# Venti_rev1.net
KiCad netlist of a schematic drawn in EAGLE
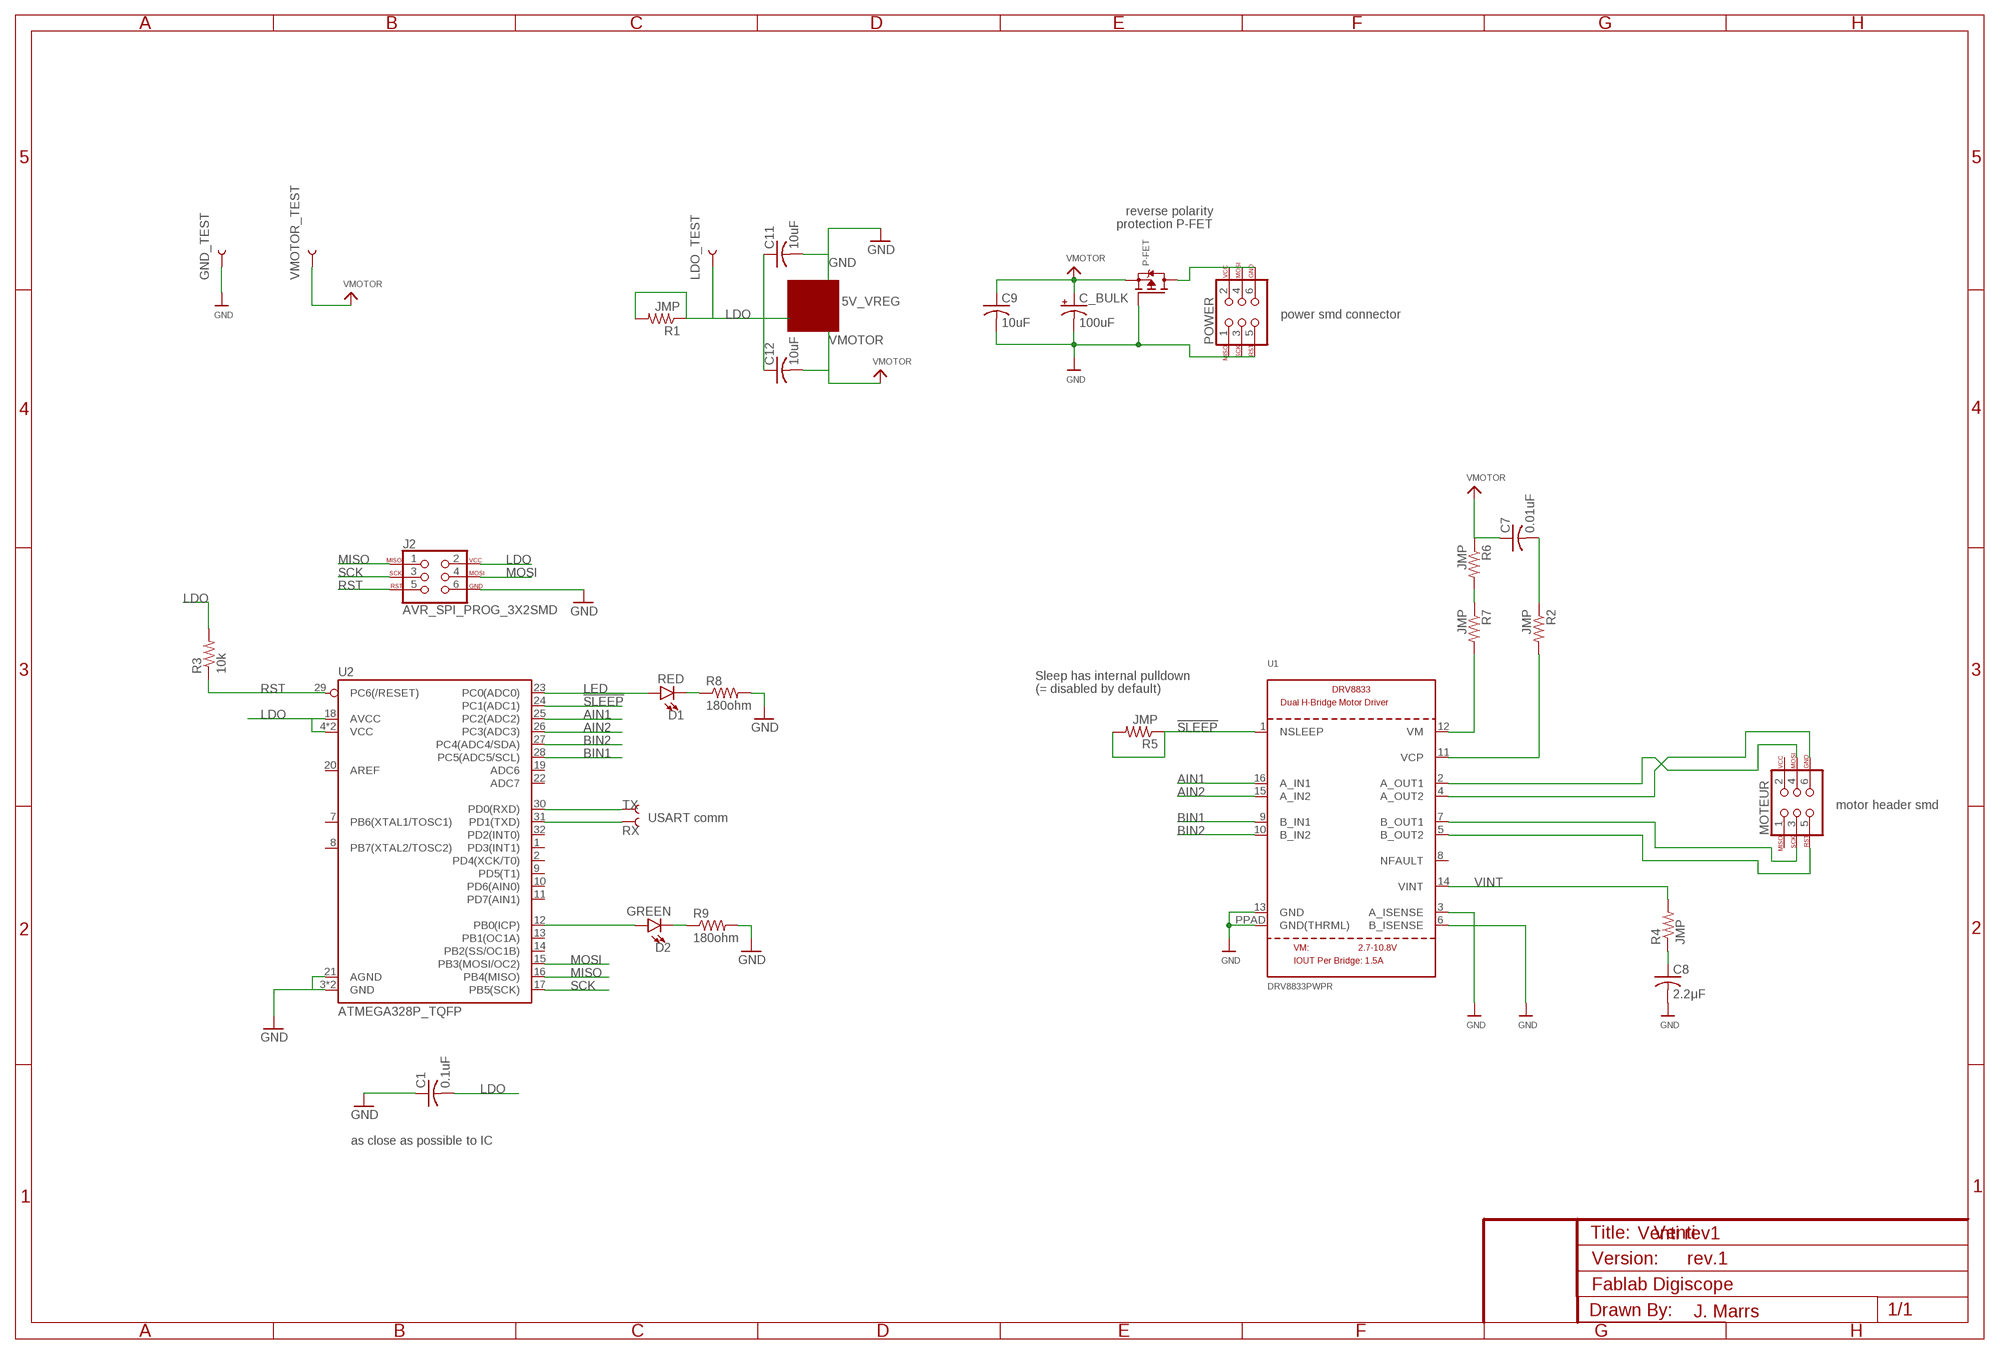
[diagram p0: schematic, sheet 1]

(export (version "E")
  (design (tool "Eeschema 10.0.6"))
  (components
    (comp (ref "5V_VREG")
      (value "MOSFET_PCH-DMG2305UX-7")
      (footprint "eagle-import:SOT23-3")
      (libsource (lib "eagle-import") (part "MOSFET_PCH-DMG2305UX-7"))
    )
    (comp (ref "C1")
      (value "0.1uF")
      (footprint "eagle-import:C1206")
      (libsource (lib "eagle-import") (part "C-USC1206"))
    )
    (comp (ref "C7")
      (value "0.01uF")
      (footprint "eagle-import:C1206")
      (libsource (lib "eagle-import") (part "C-USC1206"))
    )
    (comp (ref "C8")
      (value "2.2μF")
      (footprint "eagle-import:C1206")
      (libsource (lib "eagle-import") (part "C-USC1206"))
    )
    (comp (ref "C9")
      (value "10uF")
      (footprint "eagle-import:C1206")
      (libsource (lib "eagle-import") (part "C-USC1206"))
    )
    (comp (ref "C11")
      (value "10uF")
      (footprint "eagle-import:C1206")
      (libsource (lib "eagle-import") (part "C-USC1206"))
    )
    (comp (ref "C12")
      (value "10uF")
      (footprint "eagle-import:C1206")
      (libsource (lib "eagle-import") (part "C-USC1206"))
    )
    (comp (ref "C_BULK")
      (value "100uF")
      (footprint "eagle-import:CPOL-RADIAL-2.5MM-6.5MM")
      (libsource (lib "eagle-import") (part "100UF-POLAR-RADIAL-2.5MM-25V-20%"))
    )
    (comp (ref "D1")
      (value "RED")
      (footprint "eagle-import:LED-1206")
      (libsource (lib "eagle-import") (part "LED-RED1206"))
    )
    (comp (ref "D2")
      (value "GREEN")
      (footprint "eagle-import:LED-1206")
      (libsource (lib "eagle-import") (part "LED-RED1206"))
    )
    (comp (ref "GND_TEST")
      (value "TEST-POINT3")
      (footprint "eagle-import:PAD.03X.03")
      (libsource (lib "eagle-import") (part "TEST-POINT3"))
    )
    (comp (ref "J2")
      (value "AVR_SPI_PROG_3X2SMD")
      (footprint "eagle-import:2X3_SMT_POSTS")
      (libsource (lib "eagle-import") (part "AVR_SPI_PROG_3X2SMD"))
    )
    (comp (ref "LDO_TEST")
      (value "TEST-POINT3")
      (footprint "eagle-import:PAD.03X.03")
      (libsource (lib "eagle-import") (part "TEST-POINT3"))
    )
    (comp (ref "MOTEUR")
      (value "AVR_SPI_PROG_3X2SMD")
      (footprint "eagle-import:2X3_SMT_POSTS")
      (libsource (lib "eagle-import") (part "AVR_SPI_PROG_3X2SMD"))
    )
    (comp (ref "P-FET")
      (value "MOSFET-PWIDE")
      (footprint "eagle-import:SOT23-WIDE")
      (libsource (lib "eagle-import") (part "MOSFET-PWIDE"))
    )
    (comp (ref "POWER")
      (value "AVR_SPI_PROG_3X2SMD")
      (footprint "eagle-import:2X3_SMT_POSTS")
      (libsource (lib "eagle-import") (part "AVR_SPI_PROG_3X2SMD"))
    )
    (comp (ref "R1")
      (value "JMP")
      (footprint "eagle-import:R1206")
      (libsource (lib "eagle-import") (part "R-US_R1206"))
    )
    (comp (ref "R2")
      (value "JMP")
      (footprint "eagle-import:R1206")
      (libsource (lib "eagle-import") (part "R-US_R1206"))
    )
    (comp (ref "R3")
      (value "10k")
      (footprint "eagle-import:R1206")
      (libsource (lib "eagle-import") (part "R-US_R1206"))
    )
    (comp (ref "R4")
      (value "JMP")
      (footprint "eagle-import:R1206")
      (libsource (lib "eagle-import") (part "R-US_R1206"))
    )
    (comp (ref "R5")
      (value "JMP")
      (footprint "eagle-import:R1206")
      (libsource (lib "eagle-import") (part "R-US_R1206"))
    )
    (comp (ref "R6")
      (value "JMP")
      (footprint "eagle-import:R1206")
      (libsource (lib "eagle-import") (part "R-US_R1206"))
    )
    (comp (ref "R7")
      (value "JMP")
      (footprint "eagle-import:R1206")
      (libsource (lib "eagle-import") (part "R-US_R1206"))
    )
    (comp (ref "R8")
      (value "180ohm")
      (footprint "eagle-import:R1206")
      (libsource (lib "eagle-import") (part "R-US_R1206"))
    )
    (comp (ref "R9")
      (value "180ohm")
      (footprint "eagle-import:R1206")
      (libsource (lib "eagle-import") (part "R-US_R1206"))
    )
    (comp (ref "RX")
      (value "TEST-POINT3")
      (footprint "eagle-import:PAD.03X.03")
      (libsource (lib "eagle-import") (part "TEST-POINT3"))
    )
    (comp (ref "TX")
      (value "TEST-POINT3")
      (footprint "eagle-import:PAD.03X.03")
      (libsource (lib "eagle-import") (part "TEST-POINT3"))
    )
    (comp (ref "U1")
      (value "DRV8833PWPR")
      (footprint "eagle-import:HTSSOP16")
      (libsource (lib "eagle-import") (part "DRV8833"))
    )
    (comp (ref "U2")
      (value "ATMEGA328P_TQFP")
      (footprint "eagle-import:TQFP32-08")
      (libsource (lib "eagle-import") (part "ATMEGA328P_TQFP"))
    )
    (comp (ref "VMOTOR_TEST")
      (value "TEST-POINT3")
      (footprint "eagle-import:PAD.03X.03")
      (libsource (lib "eagle-import") (part "TEST-POINT3"))
    )
  )
  (nets
    (net (code "1") (name "/AIN1") (class "Default")
      (node (ref "U1") (pin "16") (pinfunction "A_IN1_16") (pintype "input"))
      (node (ref "U2") (pin "25") (pinfunction "PC2(ADC2)_25") (pintype "bidirectional"))
    )
    (net (code "2") (name "/AIN2") (class "Default")
      (node (ref "U1") (pin "15") (pinfunction "A_IN2_15") (pintype "input"))
      (node (ref "U2") (pin "26") (pinfunction "PC3(ADC3)_26") (pintype "bidirectional"))
    )
    (net (code "3") (name "/BIN1") (class "Default")
      (node (ref "U1") (pin "9") (pinfunction "B_IN1_9") (pintype "input"))
      (node (ref "U2") (pin "28") (pinfunction "PC5(ADC5/SCL)_28") (pintype "bidirectional"))
    )
    (net (code "4") (name "/BIN2") (class "Default")
      (node (ref "U1") (pin "10") (pinfunction "B_IN2_10") (pintype "input"))
      (node (ref "U2") (pin "27") (pinfunction "PC4(ADC4/SDA)_27") (pintype "bidirectional"))
    )
    (net (code "5") (name "/LDO") (class "Default")
      (node (ref "5V_VREG") (pin "1") (pinfunction "G_1") (pintype "bidirectional"))
      (node (ref "C1") (pin "2") (pinfunction "2_2") (pintype "passive"))
      (node (ref "C11") (pin "1") (pinfunction "1_1") (pintype "passive"))
      (node (ref "C12") (pin "1") (pinfunction "1_1") (pintype "passive"))
      (node (ref "J2") (pin "2") (pinfunction "2_2") (pintype "passive"))
      (node (ref "LDO_TEST") (pin "P$1") (pinfunction "1_P$1") (pintype "bidirectional"))
      (node (ref "R1") (pin "1") (pinfunction "1_1") (pintype "passive"))
      (node (ref "R1") (pin "2") (pinfunction "2_2") (pintype "passive"))
      (node (ref "R3") (pin "2") (pinfunction "2_2") (pintype "passive"))
      (node (ref "U2") (pin "18") (pinfunction "AVCC_18") (pintype "bidirectional"))
      (node (ref "U2") (pin "4") (pinfunction "VCC_4") (pintype "bidirectional"))
      (node (ref "U2") (pin "6") (pinfunction "VCC_6") (pintype "bidirectional"))
    )
    (net (code "6") (name "/LED") (class "Default")
      (node (ref "D1") (pin "A") (pinfunction "A_A") (pintype "passive"))
      (node (ref "U2") (pin "23") (pinfunction "PC0(ADC0)_23") (pintype "bidirectional"))
    )
    (net (code "7") (name "/MISO") (class "Default")
      (node (ref "J2") (pin "1") (pinfunction "1_1") (pintype "passive"))
      (node (ref "U2") (pin "16") (pinfunction "PB4(MISO)_16") (pintype "bidirectional"))
    )
    (net (code "8") (name "/MOSI") (class "Default")
      (node (ref "J2") (pin "4") (pinfunction "4_4") (pintype "passive"))
      (node (ref "U2") (pin "15") (pinfunction "PB3(MOSI/OC2)_15") (pintype "bidirectional"))
    )
    (net (code "9") (name "/RST") (class "Default")
      (node (ref "J2") (pin "5") (pinfunction "5_5") (pintype "passive"))
      (node (ref "R3") (pin "1") (pinfunction "1_1") (pintype "passive"))
      (node (ref "U2") (pin "29") (pinfunction "PC6(/RESET)_29") (pintype "bidirectional"))
    )
    (net (code "10") (name "/SCK") (class "Default")
      (node (ref "J2") (pin "3") (pinfunction "3_3") (pintype "passive"))
      (node (ref "U2") (pin "17") (pinfunction "PB5(SCK)_17") (pintype "bidirectional"))
    )
    (net (code "11") (name "/VINT") (class "Default")
      (node (ref "R4") (pin "2") (pinfunction "2_2") (pintype "passive"))
      (node (ref "U1") (pin "14") (pinfunction "VINT_14") (pintype "power_in"))
    )
    (net (code "12") (name "/~{SLEEP}") (class "Default")
      (node (ref "R5") (pin "1") (pinfunction "1_1") (pintype "passive"))
      (node (ref "R5") (pin "2") (pinfunction "2_2") (pintype "passive"))
      (node (ref "U1") (pin "1") (pinfunction "NSLEEP_1") (pintype "input"))
      (node (ref "U2") (pin "24") (pinfunction "PC1(ADC1)_24") (pintype "bidirectional"))
    )
    (net (code "13") (name "GND") (class "Default")
      (node (ref "5V_VREG") (pin "3") (pinfunction "D_3") (pintype "bidirectional"))
      (node (ref "C1") (pin "1") (pinfunction "1_1") (pintype "passive"))
      (node (ref "C11") (pin "2") (pinfunction "2_2") (pintype "passive"))
      (node (ref "C8") (pin "2") (pinfunction "2_2") (pintype "passive"))
      (node (ref "C9") (pin "2") (pinfunction "2_2") (pintype "passive"))
      (node (ref "C_BULK") (pin "2") (pinfunction "-_2") (pintype "passive"))
      (node (ref "GND_TEST") (pin "P$1") (pinfunction "1_P$1") (pintype "bidirectional"))
      (node (ref "J2") (pin "6") (pinfunction "6_6") (pintype "passive"))
      (node (ref "P-FET") (pin "1") (pinfunction "G_1") (pintype "passive"))
      (node (ref "POWER") (pin "1") (pinfunction "1_1") (pintype "passive"))
      (node (ref "POWER") (pin "3") (pinfunction "3_3") (pintype "passive"))
      (node (ref "POWER") (pin "5") (pinfunction "5_5") (pintype "passive"))
      (node (ref "R8") (pin "2") (pinfunction "2_2") (pintype "passive"))
      (node (ref "R9") (pin "2") (pinfunction "2_2") (pintype "passive"))
      (node (ref "U1") (pin "13") (pinfunction "GND_13") (pintype "power_in"))
      (node (ref "U1") (pin "3") (pinfunction "A_ISENSE_3") (pintype "bidirectional"))
      (node (ref "U1") (pin "6") (pinfunction "B_ISENSE_6") (pintype "bidirectional"))
      (node (ref "U1") (pin "PPAD") (pinfunction "GND(THRML)_PPAD") (pintype "power_in"))
      (node (ref "U2") (pin "21") (pinfunction "AGND_21") (pintype "bidirectional"))
      (node (ref "U2") (pin "3") (pinfunction "GND_3") (pintype "bidirectional"))
      (node (ref "U2") (pin "5") (pinfunction "GND_5") (pintype "bidirectional"))
    )
    (net (code "14") (name "Net-(C7-Pad2)") (class "Default")
      (node (ref "C7") (pin "2") (pinfunction "2_2") (pintype "passive"))
      (node (ref "R2") (pin "1") (pinfunction "1_1") (pintype "passive"))
    )
    (net (code "15") (name "Net-(C8-Pad1)") (class "Default")
      (node (ref "C8") (pin "1") (pinfunction "1_1") (pintype "passive"))
      (node (ref "R4") (pin "1") (pinfunction "1_1") (pintype "passive"))
    )
    (net (code "16") (name "Net-(D1-PadC)") (class "Default")
      (node (ref "D1") (pin "C") (pinfunction "C_C") (pintype "passive"))
      (node (ref "R8") (pin "1") (pinfunction "1_1") (pintype "passive"))
    )
    (net (code "17") (name "Net-(D2-PadC)") (class "Default")
      (node (ref "D2") (pin "C") (pinfunction "C_C") (pintype "passive"))
      (node (ref "R9") (pin "1") (pinfunction "1_1") (pintype "passive"))
    )
    (net (code "18") (name "Net-(P-FET-D)") (class "Default")
      (node (ref "P-FET") (pin "3") (pinfunction "D_3") (pintype "passive"))
      (node (ref "POWER") (pin "2") (pinfunction "2_2") (pintype "passive"))
      (node (ref "POWER") (pin "4") (pinfunction "4_4") (pintype "passive"))
      (node (ref "POWER") (pin "6") (pinfunction "6_6") (pintype "passive"))
    )
    (net (code "19") (name "Net-(R6-Pad2)") (class "Default")
      (node (ref "R6") (pin "2") (pinfunction "2_2") (pintype "passive"))
      (node (ref "R7") (pin "1") (pinfunction "1_1") (pintype "passive"))
    )
    (net (code "20") (name "Net-(RX-1)") (class "Default")
      (node (ref "RX") (pin "P$1") (pinfunction "1_P$1") (pintype "bidirectional"))
      (node (ref "U2") (pin "31") (pinfunction "PD1(TXD)_31") (pintype "bidirectional"))
    )
    (net (code "21") (name "Net-(TX-1)") (class "Default")
      (node (ref "TX") (pin "P$1") (pinfunction "1_P$1") (pintype "bidirectional"))
      (node (ref "U2") (pin "30") (pinfunction "PD0(RXD)_30") (pintype "bidirectional"))
    )
    (net (code "22") (name "Net-(U1-A_OUT1)") (class "Default")
      (node (ref "MOTEUR") (pin "4") (pinfunction "4_4") (pintype "passive"))
      (node (ref "U1") (pin "2") (pinfunction "A_OUT1_2") (pintype "output"))
    )
    (net (code "23") (name "Net-(U1-A_OUT2)") (class "Default")
      (node (ref "MOTEUR") (pin "6") (pinfunction "6_6") (pintype "passive"))
      (node (ref "U1") (pin "4") (pinfunction "A_OUT2_4") (pintype "output"))
    )
    (net (code "24") (name "Net-(U1-B_OUT1)") (class "Default")
      (node (ref "MOTEUR") (pin "3") (pinfunction "3_3") (pintype "passive"))
      (node (ref "U1") (pin "7") (pinfunction "B_OUT1_7") (pintype "output"))
    )
    (net (code "25") (name "Net-(U1-B_OUT2)") (class "Default")
      (node (ref "MOTEUR") (pin "5") (pinfunction "5_5") (pintype "passive"))
      (node (ref "U1") (pin "5") (pinfunction "B_OUT2_5") (pintype "output"))
    )
    (net (code "26") (name "Net-(U1-VCP)") (class "Default")
      (node (ref "R2") (pin "2") (pinfunction "2_2") (pintype "passive"))
      (node (ref "U1") (pin "11") (pinfunction "VCP_11") (pintype "bidirectional"))
    )
    (net (code "27") (name "Net-(U1-VM)") (class "Default")
      (node (ref "R7") (pin "2") (pinfunction "2_2") (pintype "passive"))
      (node (ref "U1") (pin "12") (pinfunction "VM_12") (pintype "power_in"))
    )
    (net (code "28") (name "Net-(U2-PB0(ICP))") (class "Default")
      (node (ref "D2") (pin "A") (pinfunction "A_A") (pintype "passive"))
      (node (ref "U2") (pin "12") (pinfunction "PB0(ICP)_12") (pintype "bidirectional"))
    )
    (net (code "29") (name "VMOTOR") (class "Default")
      (node (ref "5V_VREG") (pin "2") (pinfunction "S_2") (pintype "bidirectional"))
      (node (ref "C12") (pin "2") (pinfunction "2_2") (pintype "passive"))
      (node (ref "C7") (pin "1") (pinfunction "1_1") (pintype "passive"))
      (node (ref "C9") (pin "1") (pinfunction "1_1") (pintype "passive"))
      (node (ref "C_BULK") (pin "1") (pinfunction "+_1") (pintype "passive"))
      (node (ref "P-FET") (pin "2") (pinfunction "S_2") (pintype "passive"))
      (node (ref "R6") (pin "1") (pinfunction "1_1") (pintype "passive"))
      (node (ref "VMOTOR_TEST") (pin "P$1") (pinfunction "1_P$1") (pintype "bidirectional"))
    )
    (net (code "30") (name "unconnected-(MOTEUR-Pad1)") (class "Default")
      (node (ref "MOTEUR") (pin "1") (pinfunction "1_1") (pintype "passive"))
    )
    (net (code "31") (name "unconnected-(MOTEUR-Pad2)") (class "Default")
      (node (ref "MOTEUR") (pin "2") (pinfunction "2_2") (pintype "passive"))
    )
    (net (code "32") (name "unconnected-(U1-NFAULT-Pad8)") (class "Default")
      (node (ref "U1") (pin "8") (pinfunction "NFAULT_8") (pintype "bidirectional"))
    )
    (net (code "33") (name "unconnected-(U2-ADC6-Pad19)") (class "Default")
      (node (ref "U2") (pin "19") (pinfunction "ADC6_19") (pintype "bidirectional"))
    )
    (net (code "34") (name "unconnected-(U2-ADC7-Pad22)") (class "Default")
      (node (ref "U2") (pin "22") (pinfunction "ADC7_22") (pintype "bidirectional"))
    )
    (net (code "35") (name "unconnected-(U2-AREF-Pad20)") (class "Default")
      (node (ref "U2") (pin "20") (pinfunction "AREF_20") (pintype "bidirectional"))
    )
    (net (code "36") (name "unconnected-(U2-PB1(OC1A)-Pad13)") (class "Default")
      (node (ref "U2") (pin "13") (pinfunction "PB1(OC1A)_13") (pintype "bidirectional"))
    )
    (net (code "37") (name "unconnected-(U2-PB2(SS{slash}OC1B)-Pad14)") (class "Default")
      (node (ref "U2") (pin "14") (pinfunction "PB2(SS/OC1B)_14") (pintype "bidirectional"))
    )
    (net (code "38") (name "unconnected-(U2-PB6(XTAL1{slash}TOSC1)-Pad7)") (class "Default")
      (node (ref "U2") (pin "7") (pinfunction "PB6(XTAL1/TOSC1)_7") (pintype "bidirectional"))
    )
    (net (code "39") (name "unconnected-(U2-PB7(XTAL2{slash}TOSC2)-Pad8)") (class "Default")
      (node (ref "U2") (pin "8") (pinfunction "PB7(XTAL2/TOSC2)_8") (pintype "bidirectional"))
    )
    (net (code "40") (name "unconnected-(U2-PD2(INT0)-Pad32)") (class "Default")
      (node (ref "U2") (pin "32") (pinfunction "PD2(INT0)_32") (pintype "bidirectional"))
    )
    (net (code "41") (name "unconnected-(U2-PD3(INT1)-Pad1)") (class "Default")
      (node (ref "U2") (pin "1") (pinfunction "PD3(INT1)_1") (pintype "bidirectional"))
    )
    (net (code "42") (name "unconnected-(U2-PD4(XCK{slash}T0)-Pad2)") (class "Default")
      (node (ref "U2") (pin "2") (pinfunction "PD4(XCK/T0)_2") (pintype "bidirectional"))
    )
    (net (code "43") (name "unconnected-(U2-PD5(T1)-Pad9)") (class "Default")
      (node (ref "U2") (pin "9") (pinfunction "PD5(T1)_9") (pintype "bidirectional"))
    )
    (net (code "44") (name "unconnected-(U2-PD6(AIN0)-Pad10)") (class "Default")
      (node (ref "U2") (pin "10") (pinfunction "PD6(AIN0)_10") (pintype "bidirectional"))
    )
    (net (code "45") (name "unconnected-(U2-PD7(AIN1)-Pad11)") (class "Default")
      (node (ref "U2") (pin "11") (pinfunction "PD7(AIN1)_11") (pintype "bidirectional"))
    )
  )
)
